# Breakout.net
KiCad netlist of a schematic drawn in EAGLE
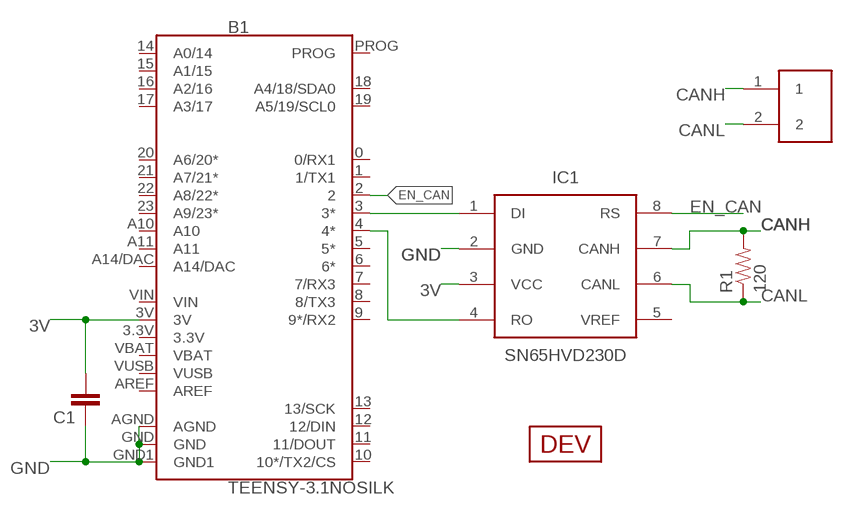
[diagram p0: schematic, sheet 1]

(export (version "E")
  (design (tool "Eeschema 10.0.6"))
  (components
    (comp (ref "B1")
      (value "TEENSY-3.1NOSILK")
      (footprint "eagle-import:TEENSY-3.1_NOSILK")
      (libsource (lib "eagle-import") (part "TEENSY-3.1NOSILK"))
    )
    (comp (ref "C1")
      (value "CAP0603-CAP")
      (footprint "eagle-import:0603-CAP")
      (libsource (lib "eagle-import") (part "CAP0603-CAP"))
    )
    (comp (ref "IC1")
      (value "SN65HVD230D")
      (footprint "eagle-import:SO-8")
      (libsource (lib "eagle-import") (part "SN65HVD23D0"))
    )
    (comp (ref "R1")
      (value "120")
      (footprint "eagle-import:0603-RES")
      (libsource (lib "eagle-import") (part "RESISTOR0603-RES"))
    )
    (comp (ref "U$1")
      (value "HEADER2")
      (footprint "eagle-import:2PINVALULOK")
      (libsource (lib "eagle-import") (part "HEADER2"))
    )
    (comp (ref "U$2")
      (value "DEV")
      (footprint "eagle-import:DEV")
      (libsource (lib "eagle-import") (part "DEV"))
    )
  )
  (nets
    (net (code "1") (name "/3.3V") (class "Default")
      (node (ref "B1") (pin "3.3V") (pinfunction "3.3V_3.3V") (pintype "power_in"))
    )
    (net (code "2") (name "/3V") (class "Default")
      (node (ref "B1") (pin "3V") (pinfunction "3V_3V") (pintype "power_in"))
      (node (ref "C1") (pin "2") (pinfunction "2_2") (pintype "passive"))
      (node (ref "IC1") (pin "3") (pinfunction "VCC_3") (pintype "power_in"))
    )
    (net (code "3") (name "/CANH") (class "Default")
      (node (ref "IC1") (pin "7") (pinfunction "CANH_7") (pintype "bidirectional"))
      (node (ref "R1") (pin "2") (pinfunction "2_2") (pintype "passive"))
      (node (ref "U$1") (pin "1") (pinfunction "1_1") (pintype "bidirectional"))
    )
    (net (code "4") (name "/CANL") (class "Default")
      (node (ref "IC1") (pin "6") (pinfunction "CANL_6") (pintype "bidirectional"))
      (node (ref "R1") (pin "1") (pinfunction "1_1") (pintype "passive"))
      (node (ref "U$1") (pin "2") (pinfunction "2_2") (pintype "bidirectional"))
    )
    (net (code "5") (name "/GND") (class "Default")
      (node (ref "B1") (pin "AGND") (pinfunction "AGND_AGND") (pintype "power_in"))
      (node (ref "B1") (pin "GND") (pinfunction "GND_GND") (pintype "power_in"))
      (node (ref "B1") (pin "GND1") (pinfunction "GND1_GND1") (pintype "power_in"))
      (node (ref "C1") (pin "1") (pinfunction "1_1") (pintype "passive"))
      (node (ref "IC1") (pin "2") (pinfunction "GND_2") (pintype "power_in"))
    )
    (net (code "6") (name "/VBAT") (class "Default")
      (node (ref "B1") (pin "VBAT") (pinfunction "VBAT_VBAT") (pintype "power_in"))
    )
    (net (code "7") (name "/VIN") (class "Default")
      (node (ref "B1") (pin "VIN") (pinfunction "VIN_VIN") (pintype "power_in"))
    )
    (net (code "8") (name "/VUSB") (class "Default")
      (node (ref "B1") (pin "VUSB") (pinfunction "VUSB_VUSB") (pintype "power_in"))
    )
    (net (code "9") (name "EN_CAN") (class "Default")
      (node (ref "B1") (pin "2") (pinfunction "2_2") (pintype "bidirectional"))
      (node (ref "IC1") (pin "8") (pinfunction "RS_8") (pintype "input"))
    )
    (net (code "10") (name "Net-(B1-3*)") (class "Default")
      (node (ref "B1") (pin "3") (pinfunction "3*_3") (pintype "bidirectional"))
      (node (ref "IC1") (pin "1") (pinfunction "DI_1") (pintype "input"))
    )
    (net (code "11") (name "Net-(B1-4*)") (class "Default")
      (node (ref "B1") (pin "4") (pinfunction "4*_4") (pintype "bidirectional"))
      (node (ref "IC1") (pin "4") (pinfunction "RO_4") (pintype "output"))
    )
    (net (code "12") (name "unconnected-(B1-0{slash}RX1-Pad0)") (class "Default")
      (node (ref "B1") (pin "0") (pinfunction "0/RX1_0") (pintype "bidirectional"))
    )
    (net (code "13") (name "unconnected-(B1-1{slash}TX1-Pad1)") (class "Default")
      (node (ref "B1") (pin "1") (pinfunction "1/TX1_1") (pintype "bidirectional"))
    )
    (net (code "14") (name "unconnected-(B1-5*-Pad5)") (class "Default")
      (node (ref "B1") (pin "5") (pinfunction "5*_5") (pintype "bidirectional"))
    )
    (net (code "15") (name "unconnected-(B1-6*-Pad6)") (class "Default")
      (node (ref "B1") (pin "6") (pinfunction "6*_6") (pintype "bidirectional"))
    )
    (net (code "16") (name "unconnected-(B1-7{slash}RX3-Pad7)") (class "Default")
      (node (ref "B1") (pin "7") (pinfunction "7/RX3_7") (pintype "bidirectional"))
    )
    (net (code "17") (name "unconnected-(B1-8{slash}TX3-Pad8)") (class "Default")
      (node (ref "B1") (pin "8") (pinfunction "8/TX3_8") (pintype "bidirectional"))
    )
    (net (code "18") (name "unconnected-(B1-9*{slash}RX2-Pad9)") (class "Default")
      (node (ref "B1") (pin "9") (pinfunction "9*/RX2_9") (pintype "bidirectional"))
    )
    (net (code "19") (name "unconnected-(B1-10*{slash}TX2{slash}CS-Pad10)") (class "Default")
      (node (ref "B1") (pin "10") (pinfunction "10*/TX2/CS_10") (pintype "bidirectional"))
    )
    (net (code "20") (name "unconnected-(B1-11{slash}DOUT-Pad11)") (class "Default")
      (node (ref "B1") (pin "11") (pinfunction "11/DOUT_11") (pintype "bidirectional"))
    )
    (net (code "21") (name "unconnected-(B1-12{slash}DIN-Pad12)") (class "Default")
      (node (ref "B1") (pin "12") (pinfunction "12/DIN_12") (pintype "bidirectional"))
    )
    (net (code "22") (name "unconnected-(B1-13{slash}SCK-Pad13)") (class "Default")
      (node (ref "B1") (pin "13") (pinfunction "13/SCK_13") (pintype "bidirectional"))
    )
    (net (code "23") (name "unconnected-(B1-A0{slash}14-Pad14)") (class "Default")
      (node (ref "B1") (pin "14") (pinfunction "A0/14_14") (pintype "bidirectional"))
    )
    (net (code "24") (name "unconnected-(B1-A1{slash}15-Pad15)") (class "Default")
      (node (ref "B1") (pin "15") (pinfunction "A1/15_15") (pintype "bidirectional"))
    )
    (net (code "25") (name "unconnected-(B1-A2{slash}16-Pad16)") (class "Default")
      (node (ref "B1") (pin "16") (pinfunction "A2/16_16") (pintype "bidirectional"))
    )
    (net (code "26") (name "unconnected-(B1-A3{slash}17-Pad17)") (class "Default")
      (node (ref "B1") (pin "17") (pinfunction "A3/17_17") (pintype "bidirectional"))
    )
    (net (code "27") (name "unconnected-(B1-A4{slash}18{slash}SDA0-Pad18)") (class "Default")
      (node (ref "B1") (pin "18") (pinfunction "A4/18/SDA0_18") (pintype "bidirectional"))
    )
    (net (code "28") (name "unconnected-(B1-A5{slash}19{slash}SCL0-Pad19)") (class "Default")
      (node (ref "B1") (pin "19") (pinfunction "A5/19/SCL0_19") (pintype "bidirectional"))
    )
    (net (code "29") (name "unconnected-(B1-A6{slash}20*-Pad20)") (class "Default")
      (node (ref "B1") (pin "20") (pinfunction "A6/20*_20") (pintype "bidirectional"))
    )
    (net (code "30") (name "unconnected-(B1-A7{slash}21*-Pad21)") (class "Default")
      (node (ref "B1") (pin "21") (pinfunction "A7/21*_21") (pintype "bidirectional"))
    )
    (net (code "31") (name "unconnected-(B1-A8{slash}22*-Pad22)") (class "Default")
      (node (ref "B1") (pin "22") (pinfunction "A8/22*_22") (pintype "bidirectional"))
    )
    (net (code "32") (name "unconnected-(B1-A9{slash}23*-Pad23)") (class "Default")
      (node (ref "B1") (pin "23") (pinfunction "A9/23*_23") (pintype "bidirectional"))
    )
    (net (code "33") (name "unconnected-(B1-PadA10)") (class "Default")
      (node (ref "B1") (pin "A10") (pinfunction "A10_A10") (pintype "bidirectional"))
    )
    (net (code "34") (name "unconnected-(B1-PadA11)") (class "Default")
      (node (ref "B1") (pin "A11") (pinfunction "A11_A11") (pintype "bidirectional"))
    )
    (net (code "35") (name "unconnected-(B1-PadA14{slash}DAC)") (class "Default")
      (node (ref "B1") (pin "A14/DAC") (pinfunction "A14/DAC_A14/DAC") (pintype "bidirectional"))
    )
    (net (code "36") (name "unconnected-(B1-PadAREF)") (class "Default")
      (node (ref "B1") (pin "AREF") (pinfunction "AREF_AREF") (pintype "bidirectional"))
    )
    (net (code "37") (name "unconnected-(B1-PadPROG)") (class "Default")
      (node (ref "B1") (pin "PROG") (pinfunction "PROG_PROG") (pintype "bidirectional"))
    )
    (net (code "38") (name "unconnected-(IC1-VREF-Pad5)") (class "Default")
      (node (ref "IC1") (pin "5") (pinfunction "VREF_5") (pintype "output"))
    )
  )
)
